# DynamicRdsBoard.net
KiCad netlist of a schematic drawn in EAGLE
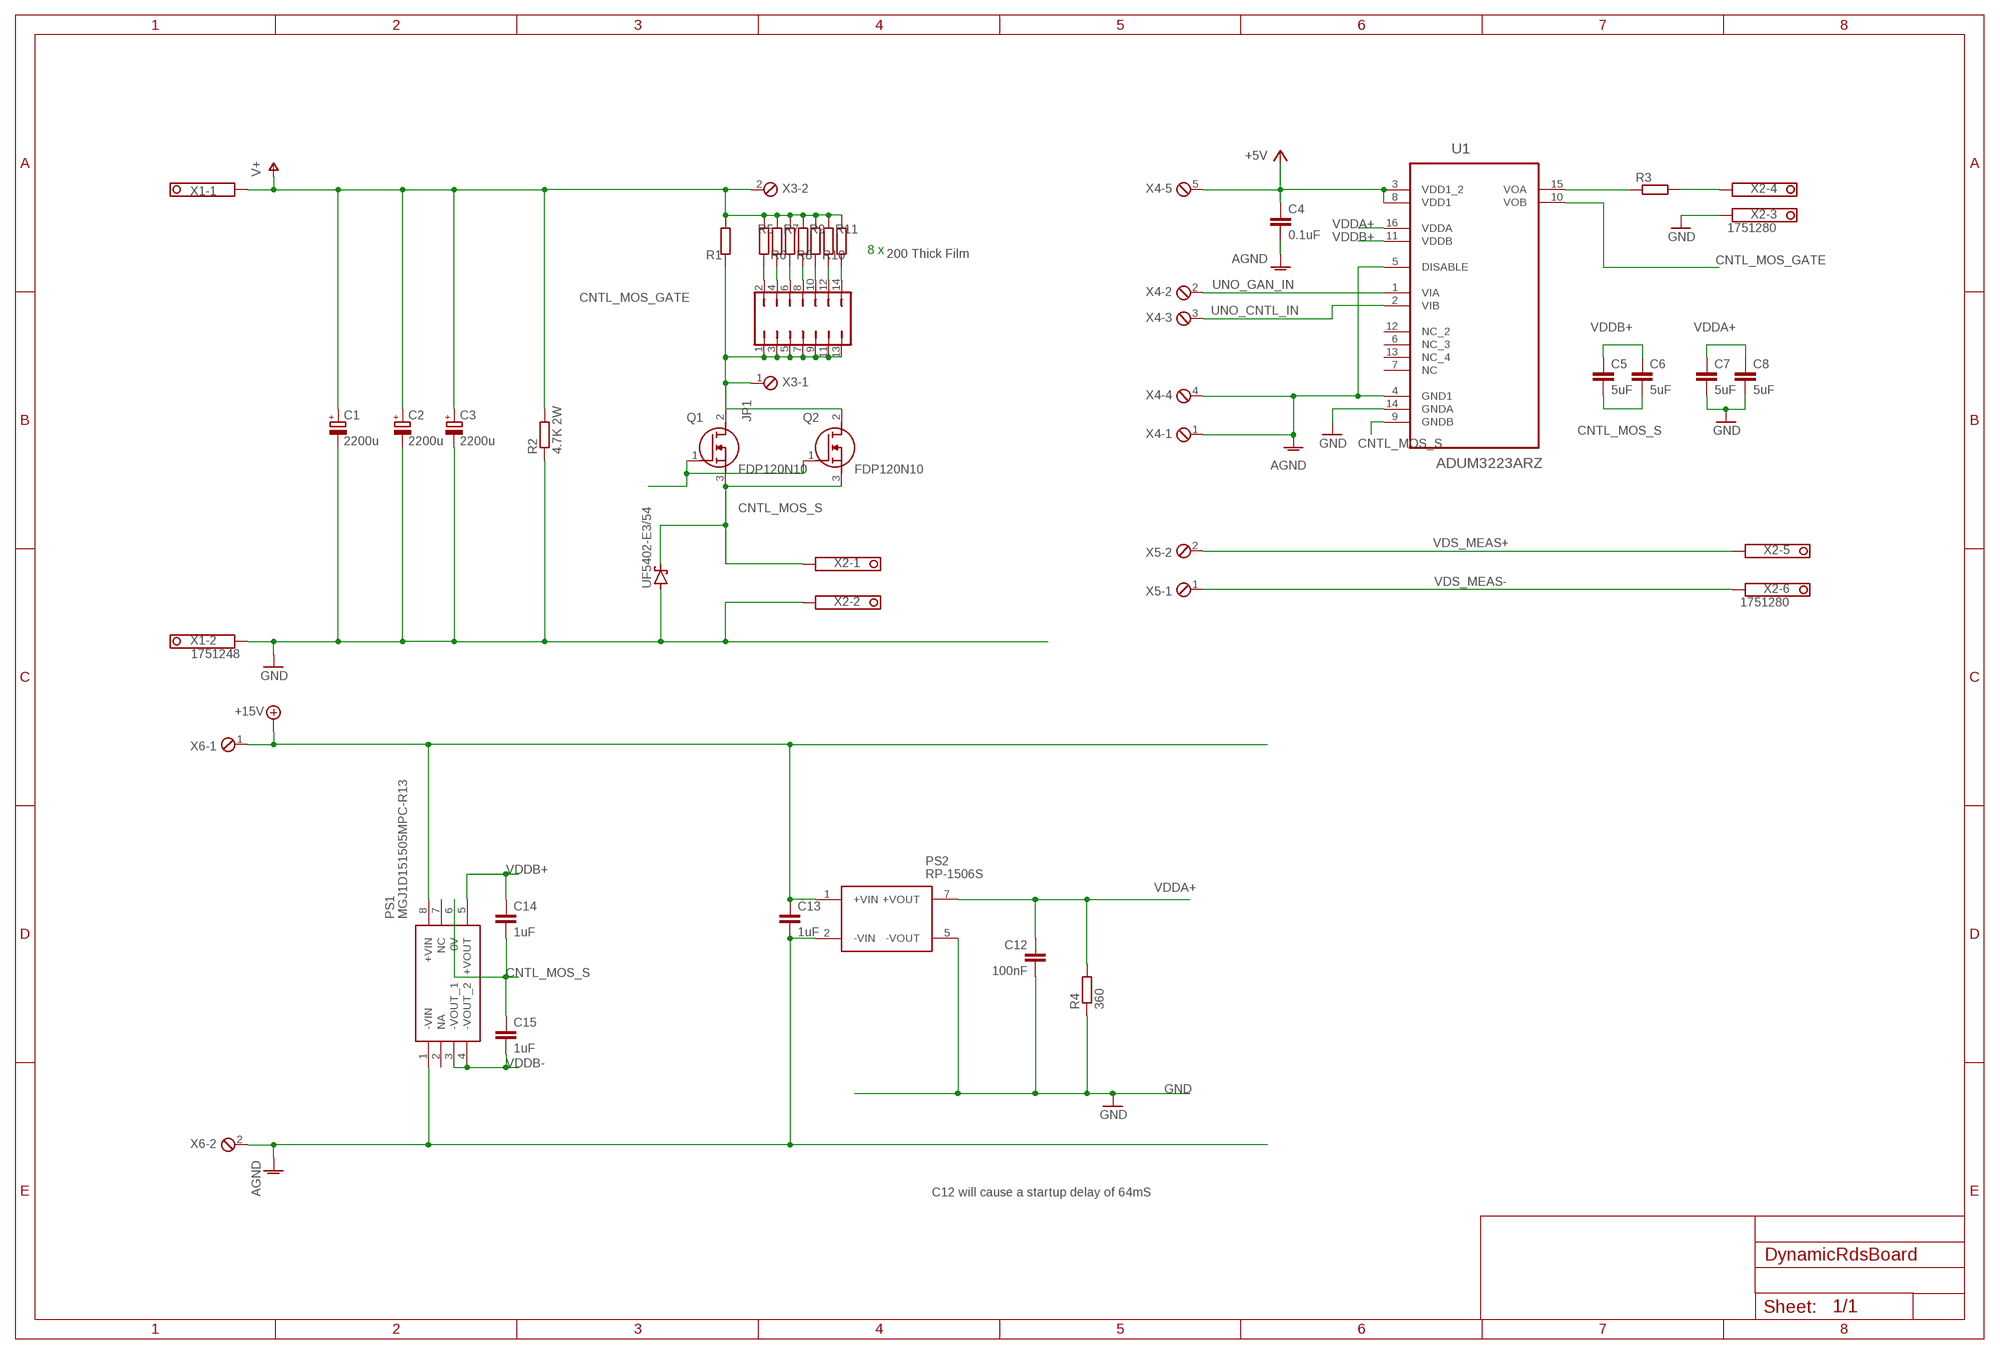
[diagram p0: schematic, sheet 1]

(export (version "E")
  (design (tool "Eeschema 10.0.6"))
  (components
    (comp (ref "C1")
      (value "2200u")
      (footprint "eagle-import:EB30D")
      (libsource (lib "eagle-import") (part "CPOL-EUE10-30"))
    )
    (comp (ref "C2")
      (value "2200u")
      (footprint "eagle-import:EB30D")
      (libsource (lib "eagle-import") (part "CPOL-EUE10-30"))
    )
    (comp (ref "C3")
      (value "2200u")
      (footprint "eagle-import:EB30D")
      (libsource (lib "eagle-import") (part "CPOL-EUE10-30"))
    )
    (comp (ref "C4")
      (value "0.1uF")
      (footprint "eagle-import:C0805")
      (libsource (lib "eagle-import") (part "C-EUC0805"))
    )
    (comp (ref "C5")
      (value "5uF")
      (footprint "eagle-import:C0805")
      (libsource (lib "eagle-import") (part "C-EUC0805"))
    )
    (comp (ref "C6")
      (value "5uF")
      (footprint "eagle-import:C0805")
      (libsource (lib "eagle-import") (part "C-EUC0805"))
    )
    (comp (ref "C7")
      (value "5uF")
      (footprint "eagle-import:C0805")
      (libsource (lib "eagle-import") (part "C-EUC0805"))
    )
    (comp (ref "C8")
      (value "5uF")
      (footprint "eagle-import:C0805")
      (libsource (lib "eagle-import") (part "C-EUC0805"))
    )
    (comp (ref "C12")
      (value "100nF")
      (footprint "eagle-import:C0805")
      (libsource (lib "eagle-import") (part "C-EUC0805"))
    )
    (comp (ref "C13")
      (value "1uF")
      (footprint "eagle-import:C0805")
      (libsource (lib "eagle-import") (part "C-EUC0805"))
    )
    (comp (ref "C14")
      (value "1uF")
      (footprint "eagle-import:C0805")
      (libsource (lib "eagle-import") (part "C-EUC0805"))
    )
    (comp (ref "C15")
      (value "1uF")
      (footprint "eagle-import:C0805")
      (libsource (lib "eagle-import") (part "C-EUC0805"))
    )
    (comp (ref "JP1")
      (value "JP7Q")
      (footprint "eagle-import:JP7Q")
      (libsource (lib "eagle-import") (part "JP7Q"))
    )
    (comp (ref "PS1")
      (value "MGJ1D151505MPC-R13")
      (footprint "eagle-import:MGJ1D151505MPCR13")
      (fields (field (name "MOUSER_PART_NUMBER") "580-MGJ1D151505MPC13"))
      (libsource (lib "eagle-import") (part "MGJ1D151505MPC-R13"))
    )
    (comp (ref "PS2")
      (value "RP-1506S")
      (footprint "eagle-import:RP1506S")
      (fields (field (name "RS_PART_NUMBER") "1655101"))
      (libsource (lib "eagle-import") (part "RP-1506S"))
    )
    (comp (ref "Q1")
      (value "FDP120N10")
      (footprint "eagle-import:TO254P483X1016X2261-3P")
      (fields (field (name "MOUSER_PART_NUMBER") "512-FDP120N10"))
      (libsource (lib "eagle-import") (part "FDP120N10"))
    )
    (comp (ref "Q2")
      (value "FDP120N10")
      (footprint "eagle-import:TO254P483X1016X2261-3P")
      (fields (field (name "MOUSER_PART_NUMBER") "512-FDP120N10"))
      (libsource (lib "eagle-import") (part "FDP120N10"))
    )
    (comp (ref "R1")
      (value "200 Thick Film")
      (footprint "eagle-import:R1206")
      (libsource (lib "eagle-import") (part "R-EU_R1206"))
    )
    (comp (ref "R2")
      (value "4.7K 2W")
      (footprint "eagle-import:0309_12")
      (libsource (lib "eagle-import") (part "R-EU_0309/12"))
    )
    (comp (ref "R3")
      (value "R-EU_R0805")
      (footprint "eagle-import:R0805")
      (libsource (lib "eagle-import") (part "R-EU_R0805"))
    )
    (comp (ref "R4")
      (value "360")
      (footprint "eagle-import:R0805")
      (libsource (lib "eagle-import") (part "R-EU_R0805"))
    )
    (comp (ref "R5")
      (value "200 Thick Film")
      (footprint "eagle-import:R1206")
      (libsource (lib "eagle-import") (part "R-EU_R1206"))
    )
    (comp (ref "R6")
      (value "200 Thick Film")
      (footprint "eagle-import:R1206")
      (libsource (lib "eagle-import") (part "R-EU_R1206"))
    )
    (comp (ref "R7")
      (value "200 Thick Film")
      (footprint "eagle-import:R1206")
      (libsource (lib "eagle-import") (part "R-EU_R1206"))
    )
    (comp (ref "R8")
      (value "200 Thick Film")
      (footprint "eagle-import:R1206")
      (libsource (lib "eagle-import") (part "R-EU_R1206"))
    )
    (comp (ref "R9")
      (value "200 Thick Film")
      (footprint "eagle-import:R1206")
      (libsource (lib "eagle-import") (part "R-EU_R1206"))
    )
    (comp (ref "R10")
      (value "200 Thick Film")
      (footprint "eagle-import:R1206")
      (libsource (lib "eagle-import") (part "R-EU_R1206"))
    )
    (comp (ref "R11")
      (value "200 Thick Film")
      (footprint "eagle-import:R1206")
      (libsource (lib "eagle-import") (part "R-EU_R1206"))
    )
    (comp (ref "U1")
      (value "ADUM3223ARZ")
      (footprint "eagle-import:SOIC127P600X175-16N")
      (fields (field (name "MF") "Analog Devices"))
      (libsource (lib "eagle-import") (part "ADUM3223ARZ"))
    )
    (comp (ref "UF5402-E3/54")
      (value "SCHOTTKY-DIODECB429-15")
      (footprint "eagle-import:CB429-15")
      (libsource (lib "eagle-import") (part "SCHOTTKY-DIODECB429-15"))
    )
    (comp (ref "X1")
      (value "1751248")
      (footprint "eagle-import:1751248")
      (libsource (lib "eagle-import") (part "1751248"))
    )
    (comp (ref "X2")
      (value "1751280")
      (footprint "eagle-import:1751280")
      (libsource (lib "eagle-import") (part "1751280"))
    )
    (comp (ref "X3")
      (value "MPT2")
      (footprint "eagle-import:2POL254")
      (libsource (lib "eagle-import") (part "MPT2"))
    )
    (comp (ref "X4")
      (value "MPT5")
      (footprint "eagle-import:5POL254")
      (libsource (lib "eagle-import") (part "MPT5"))
    )
    (comp (ref "X5")
      (value "MPT2")
      (footprint "eagle-import:2POL254")
      (libsource (lib "eagle-import") (part "MPT2"))
    )
    (comp (ref "X6")
      (value "MPT2")
      (footprint "eagle-import:2POL254")
      (libsource (lib "eagle-import") (part "MPT2"))
    )
  )
  (nets
    (net (code "1") (name "+5V") (class "Default")
      (node (ref "C4") (pin "1") (pinfunction "1_1") (pintype "passive"))
      (node (ref "U1") (pin "3") (pinfunction "VDD1_2_3") (pintype "power_in"))
      (node (ref "U1") (pin "8") (pinfunction "VDD1_8") (pintype "power_in"))
      (node (ref "X4") (pin "5") (pinfunction "1_5") (pintype "passive"))
    )
    (net (code "2") (name "+15V") (class "Default")
      (node (ref "C13") (pin "1") (pinfunction "1_1") (pintype "passive"))
      (node (ref "PS1") (pin "8") (pinfunction "+VIN_8") (pintype "bidirectional"))
      (node (ref "PS2") (pin "1") (pinfunction "+VIN_1") (pintype "bidirectional"))
      (node (ref "X6") (pin "1") (pinfunction "1_1") (pintype "passive"))
    )
    (net (code "3") (name "/CNTL_MOS_GATE") (class "Default")
      (node (ref "Q1") (pin "1") (pinfunction "G_1") (pintype "bidirectional"))
      (node (ref "Q2") (pin "1") (pinfunction "G_1") (pintype "bidirectional"))
      (node (ref "U1") (pin "10") (pinfunction "VOB_10") (pintype "output"))
    )
    (net (code "4") (name "/CNTL_MOS_S") (class "Default")
      (node (ref "C14") (pin "2") (pinfunction "2_2") (pintype "passive"))
      (node (ref "C15") (pin "1") (pinfunction "1_1") (pintype "passive"))
      (node (ref "C5") (pin "2") (pinfunction "2_2") (pintype "passive"))
      (node (ref "C6") (pin "2") (pinfunction "2_2") (pintype "passive"))
      (node (ref "PS1") (pin "6") (pinfunction "0V_6") (pintype "bidirectional"))
      (node (ref "Q1") (pin "3") (pinfunction "S_3") (pintype "bidirectional"))
      (node (ref "Q2") (pin "3") (pinfunction "S_3") (pintype "bidirectional"))
      (node (ref "U1") (pin "9") (pinfunction "GNDB_9") (pintype "passive"))
      (node (ref "UF5402-E3/54") (pin "C") (pinfunction "C_C") (pintype "passive"))
      (node (ref "X2") (pin "1") (pinfunction "K_1") (pintype "passive"))
    )
    (net (code "5") (name "/UNO_CNTL_IN") (class "Default")
      (node (ref "U1") (pin "2") (pinfunction "VIB_2") (pintype "input"))
      (node (ref "X4") (pin "3") (pinfunction "1_3") (pintype "passive"))
    )
    (net (code "6") (name "/UNO_GAN_IN") (class "Default")
      (node (ref "U1") (pin "1") (pinfunction "VIA_1") (pintype "input"))
      (node (ref "X4") (pin "2") (pinfunction "1_2") (pintype "passive"))
    )
    (net (code "7") (name "/VDDA+") (class "Default")
      (node (ref "C12") (pin "1") (pinfunction "1_1") (pintype "passive"))
      (node (ref "C7") (pin "1") (pinfunction "1_1") (pintype "passive"))
      (node (ref "C8") (pin "1") (pinfunction "1_1") (pintype "passive"))
      (node (ref "PS2") (pin "7") (pinfunction "+VOUT_7") (pintype "bidirectional"))
      (node (ref "R4") (pin "2") (pinfunction "2_2") (pintype "passive"))
      (node (ref "U1") (pin "16") (pinfunction "VDDA_16") (pintype "power_in"))
    )
    (net (code "8") (name "/VDDB+") (class "Default")
      (node (ref "C14") (pin "1") (pinfunction "1_1") (pintype "passive"))
      (node (ref "C5") (pin "1") (pinfunction "1_1") (pintype "passive"))
      (node (ref "C6") (pin "1") (pinfunction "1_1") (pintype "passive"))
      (node (ref "PS1") (pin "5") (pinfunction "+VOUT_5") (pintype "bidirectional"))
      (node (ref "U1") (pin "11") (pinfunction "VDDB_11") (pintype "power_in"))
    )
    (net (code "9") (name "/VDDB-") (class "Default")
      (node (ref "C15") (pin "2") (pinfunction "2_2") (pintype "passive"))
      (node (ref "PS1") (pin "3") (pinfunction "-VOUT_1_3") (pintype "bidirectional"))
      (node (ref "PS1") (pin "4") (pinfunction "-VOUT_2_4") (pintype "bidirectional"))
    )
    (net (code "10") (name "/VDS_MEAS+") (class "Default")
      (node (ref "X2") (pin "5") (pinfunction "K_5") (pintype "passive"))
      (node (ref "X5") (pin "2") (pinfunction "1_2") (pintype "passive"))
    )
    (net (code "11") (name "/VDS_MEAS-") (class "Default")
      (node (ref "X2") (pin "6") (pinfunction "K_6") (pintype "passive"))
      (node (ref "X5") (pin "1") (pinfunction "1_1") (pintype "passive"))
    )
    (net (code "12") (name "AGND") (class "Default")
      (node (ref "C13") (pin "2") (pinfunction "2_2") (pintype "passive"))
      (node (ref "C4") (pin "2") (pinfunction "2_2") (pintype "passive"))
      (node (ref "PS1") (pin "1") (pinfunction "-VIN_1") (pintype "bidirectional"))
      (node (ref "PS2") (pin "2") (pinfunction "-VIN_2") (pintype "bidirectional"))
      (node (ref "U1") (pin "4") (pinfunction "GND1_4") (pintype "passive"))
      (node (ref "U1") (pin "5") (pinfunction "DISABLE_5") (pintype "input"))
      (node (ref "X4") (pin "1") (pinfunction "1_1") (pintype "passive"))
      (node (ref "X4") (pin "4") (pinfunction "1_4") (pintype "passive"))
      (node (ref "X6") (pin "2") (pinfunction "1_2") (pintype "passive"))
    )
    (net (code "13") (name "GND") (class "Default")
      (node (ref "C1") (pin "-") (pinfunction "-_-") (pintype "passive"))
      (node (ref "C12") (pin "2") (pinfunction "2_2") (pintype "passive"))
      (node (ref "C2") (pin "-") (pinfunction "-_-") (pintype "passive"))
      (node (ref "C3") (pin "-") (pinfunction "-_-") (pintype "passive"))
      (node (ref "C7") (pin "2") (pinfunction "2_2") (pintype "passive"))
      (node (ref "C8") (pin "2") (pinfunction "2_2") (pintype "passive"))
      (node (ref "PS2") (pin "5") (pinfunction "-VOUT_5") (pintype "bidirectional"))
      (node (ref "R2") (pin "1") (pinfunction "1_1") (pintype "passive"))
      (node (ref "R4") (pin "1") (pinfunction "1_1") (pintype "passive"))
      (node (ref "U1") (pin "14") (pinfunction "GNDA_14") (pintype "passive"))
      (node (ref "UF5402-E3/54") (pin "A") (pinfunction "A_A") (pintype "passive"))
      (node (ref "X1") (pin "2") (pinfunction "K_2") (pintype "passive"))
      (node (ref "X2") (pin "2") (pinfunction "K_2") (pintype "passive"))
      (node (ref "X2") (pin "3") (pinfunction "K_3") (pintype "passive"))
    )
    (net (code "14") (name "Net-(JP1-Pad2)") (class "Default")
      (node (ref "JP1") (pin "2") (pinfunction "2_2") (pintype "passive"))
      (node (ref "R5") (pin "1") (pinfunction "1_1") (pintype "passive"))
    )
    (net (code "15") (name "Net-(JP1-Pad4)") (class "Default")
      (node (ref "JP1") (pin "4") (pinfunction "4_4") (pintype "passive"))
      (node (ref "R6") (pin "1") (pinfunction "1_1") (pintype "passive"))
    )
    (net (code "16") (name "Net-(JP1-Pad6)") (class "Default")
      (node (ref "JP1") (pin "6") (pinfunction "6_6") (pintype "passive"))
      (node (ref "R7") (pin "1") (pinfunction "1_1") (pintype "passive"))
    )
    (net (code "17") (name "Net-(JP1-Pad8)") (class "Default")
      (node (ref "JP1") (pin "8") (pinfunction "8_8") (pintype "passive"))
      (node (ref "R8") (pin "1") (pinfunction "1_1") (pintype "passive"))
    )
    (net (code "18") (name "Net-(JP1-Pad10)") (class "Default")
      (node (ref "JP1") (pin "10") (pinfunction "10_10") (pintype "passive"))
      (node (ref "R9") (pin "1") (pinfunction "1_1") (pintype "passive"))
    )
    (net (code "19") (name "Net-(JP1-Pad12)") (class "Default")
      (node (ref "JP1") (pin "12") (pinfunction "12_12") (pintype "passive"))
      (node (ref "R10") (pin "1") (pinfunction "1_1") (pintype "passive"))
    )
    (net (code "20") (name "Net-(JP1-Pad14)") (class "Default")
      (node (ref "JP1") (pin "14") (pinfunction "14_14") (pintype "passive"))
      (node (ref "R11") (pin "1") (pinfunction "1_1") (pintype "passive"))
    )
    (net (code "21") (name "Net-(Q1-D)") (class "Default")
      (node (ref "JP1") (pin "1") (pinfunction "1_1") (pintype "passive"))
      (node (ref "JP1") (pin "11") (pinfunction "11_11") (pintype "passive"))
      (node (ref "JP1") (pin "13") (pinfunction "13_13") (pintype "passive"))
      (node (ref "JP1") (pin "3") (pinfunction "3_3") (pintype "passive"))
      (node (ref "JP1") (pin "5") (pinfunction "5_5") (pintype "passive"))
      (node (ref "JP1") (pin "7") (pinfunction "7_7") (pintype "passive"))
      (node (ref "JP1") (pin "9") (pinfunction "9_9") (pintype "passive"))
      (node (ref "Q1") (pin "2") (pinfunction "D_2") (pintype "bidirectional"))
      (node (ref "Q2") (pin "2") (pinfunction "D_2") (pintype "bidirectional"))
      (node (ref "R1") (pin "1") (pinfunction "1_1") (pintype "passive"))
      (node (ref "X3") (pin "1") (pinfunction "1_1") (pintype "passive"))
    )
    (net (code "22") (name "Net-(U1-VOA)") (class "Default")
      (node (ref "R3") (pin "1") (pinfunction "1_1") (pintype "passive"))
      (node (ref "U1") (pin "15") (pinfunction "VOA_15") (pintype "output"))
    )
    (net (code "23") (name "Net-(X2D-K)") (class "Default")
      (node (ref "R3") (pin "2") (pinfunction "2_2") (pintype "passive"))
      (node (ref "X2") (pin "4") (pinfunction "K_4") (pintype "passive"))
    )
    (net (code "24") (name "V+") (class "Default")
      (node (ref "C1") (pin "+") (pinfunction "+_+") (pintype "passive"))
      (node (ref "C2") (pin "+") (pinfunction "+_+") (pintype "passive"))
      (node (ref "C3") (pin "+") (pinfunction "+_+") (pintype "passive"))
      (node (ref "R1") (pin "2") (pinfunction "2_2") (pintype "passive"))
      (node (ref "R10") (pin "2") (pinfunction "2_2") (pintype "passive"))
      (node (ref "R11") (pin "2") (pinfunction "2_2") (pintype "passive"))
      (node (ref "R2") (pin "2") (pinfunction "2_2") (pintype "passive"))
      (node (ref "R5") (pin "2") (pinfunction "2_2") (pintype "passive"))
      (node (ref "R6") (pin "2") (pinfunction "2_2") (pintype "passive"))
      (node (ref "R7") (pin "2") (pinfunction "2_2") (pintype "passive"))
      (node (ref "R8") (pin "2") (pinfunction "2_2") (pintype "passive"))
      (node (ref "R9") (pin "2") (pinfunction "2_2") (pintype "passive"))
      (node (ref "X1") (pin "1") (pinfunction "K_1") (pintype "passive"))
      (node (ref "X3") (pin "2") (pinfunction "1_2") (pintype "passive"))
    )
    (net (code "25") (name "unconnected-(PS1-NA-Pad2)") (class "Default")
      (node (ref "PS1") (pin "2") (pinfunction "NA_2") (pintype "bidirectional"))
    )
    (net (code "26") (name "unconnected-(PS1-NC-Pad7)") (class "Default")
      (node (ref "PS1") (pin "7") (pinfunction "NC_7") (pintype "no_connect"))
    )
    (net (code "27") (name "unconnected-(U1-NC-Pad7)") (class "Default")
      (node (ref "U1") (pin "7") (pinfunction "NC_7") (pintype "no_connect"))
    )
    (net (code "28") (name "unconnected-(U1-NC_2-Pad12)") (class "Default")
      (node (ref "U1") (pin "12") (pinfunction "NC_2_12") (pintype "no_connect"))
    )
    (net (code "29") (name "unconnected-(U1-NC_3-Pad6)") (class "Default")
      (node (ref "U1") (pin "6") (pinfunction "NC_3_6") (pintype "no_connect"))
    )
    (net (code "30") (name "unconnected-(U1-NC_4-Pad13)") (class "Default")
      (node (ref "U1") (pin "13") (pinfunction "NC_4_13") (pintype "no_connect"))
    )
  )
)
